# OUT_HIGHPOWER.net
KiCad netlist of a schematic drawn in Altium Designer
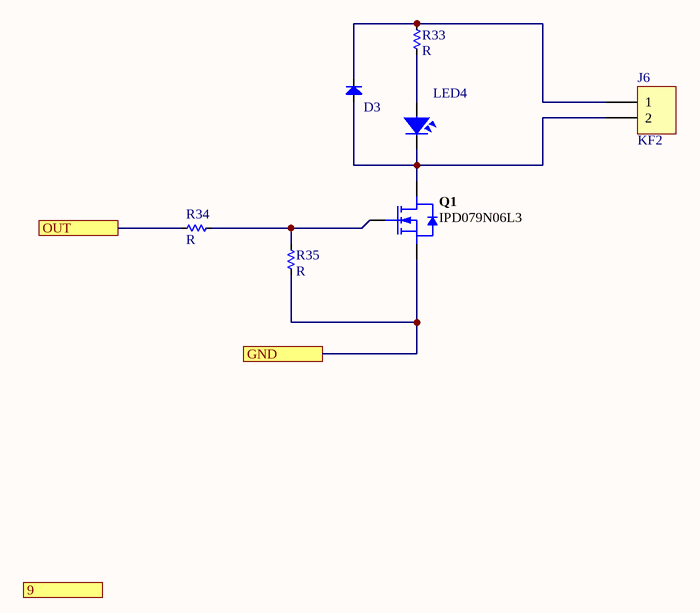
[diagram p0: OUT_HIGHPOWER.SchDoc]

(export (version "E")
  (design (tool "Eeschema 10.0.6"))
  (components
    (comp (ref "D3")
      (value "Diode")
      (footprint "DIO-SMD-106-HayDung")
      (description "Default Diode")
      (fields (field (name "PUBLISHER") "Altium Limited"))
      (libsource (lib "nhan") (part "Diode"))
    )
    (comp (ref "J6")
      (value "KF2")
      (footprint "KF2-5.08T")
      (fields
        (field (name "MANUFACTURER") "Würth Elektronik eiSos GmbH")
        (field (name "PARTNO") "691103110002")
        (field (name "CREATED BY") "Karrer Zheng")
      )
      (libsource (lib "LIBRARY") (part "KF2"))
    )
    (comp (ref "LED4") (value "LED") (footprint "LED-0805-Blue") (libsource (lib "LIBRARY") (part "LED SMD")))
    (comp (ref "Q1")
      (value "IPD079N06L3")
      (footprint "TO252-3")
      (description "IPD079N06L3 - TO-252-3")
      (libsource (lib "nhan") (part "FET_N"))
    )
    (comp (ref "R33") (value "R") (footprint "RES-SMD-0603_BIG") (libsource (lib "nhan") (part "R")))
    (comp (ref "R34") (value "R") (footprint "RES-SMD-0603_BIG") (libsource (lib "nhan") (part "R")))
    (comp (ref "R35") (value "R") (footprint "RES-SMD-0603_BIG") (libsource (lib "nhan") (part "R")))
  )
  (nets
    (net (code "2") (name "/GND") (class "Default")
      (node (ref "Q1") (pin "3") (pinfunction "S_3") (pintype "passive"))
      (node (ref "R35") (pin "1") (pinfunction "1_1") (pintype "passive"))
    )
    (net (code "3") (name "/OUT") (class "Default")
      (node (ref "R34") (pin "1") (pinfunction "1_1") (pintype "passive"))
    )
    (net (code "4") (name "Net-(D3-A)") (class "Default")
      (node (ref "D3") (pin "1") (pinfunction "A_1") (pintype "passive"))
      (node (ref "J6") (pin "2") (pinfunction "2_2") (pintype "passive"))
      (node (ref "LED4") (pin "2") (pinfunction "2_2") (pintype "passive"))
      (node (ref "Q1") (pin "2") (pinfunction "D_2") (pintype "passive"))
    )
    (net (code "5") (name "Net-(D3-K)") (class "Default")
      (node (ref "D3") (pin "2") (pinfunction "K_2") (pintype "passive"))
      (node (ref "J6") (pin "1") (pinfunction "1_1") (pintype "passive"))
      (node (ref "R33") (pin "2") (pinfunction "2_2") (pintype "passive"))
    )
    (net (code "6") (name "Net-(LED4-Pad1)") (class "Default")
      (node (ref "LED4") (pin "1") (pinfunction "1_1") (pintype "passive"))
      (node (ref "R33") (pin "1") (pinfunction "1_1") (pintype "passive"))
    )
    (net (code "7") (name "Net-(Q1-G)") (class "Default")
      (node (ref "Q1") (pin "1") (pinfunction "G_1") (pintype "passive"))
      (node (ref "R34") (pin "2") (pinfunction "2_2") (pintype "passive"))
      (node (ref "R35") (pin "2") (pinfunction "2_2") (pintype "passive"))
    )
  )
)
